# USB_UART_IMU.net
KiCad netlist of a schematic drawn in Altium Designer
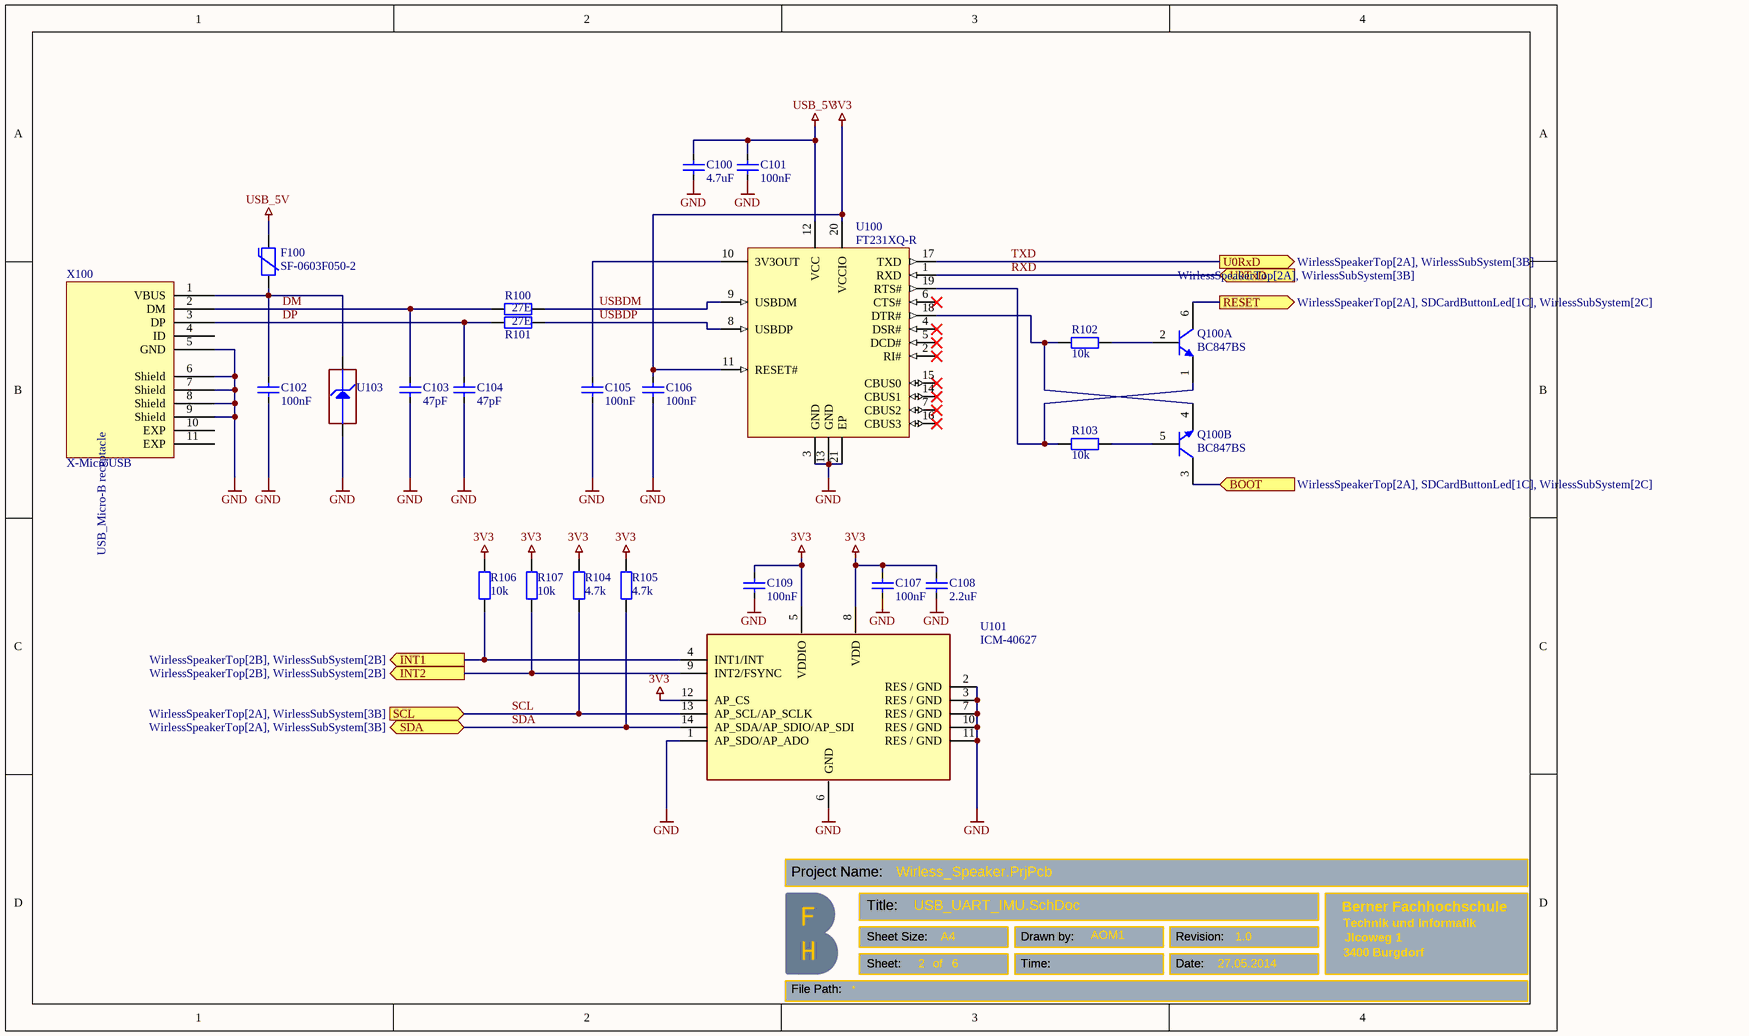
[diagram p0: USB_UART_IMU.SchDoc]

(export (version "E")
  (design (tool "Eeschema 10.0.6"))
  (components
    (comp (ref "C100")
      (value "4.7uF")
      (footprint "C-0603")
      (description "Multilayer Ceramic Capacitors MLCC")
      (fields (field (name "MANUFACTURER") "Murata Electronics") (field (name "MFR. PART NO.") "GRM18..."))
      (libsource (lib "WirelessAudioSpeaker") (part "C-SMD-0603"))
    )
    (comp (ref "C101")
      (value "100nF")
      (footprint "C-0603")
      (description "Multilayer Ceramic Capacitors MLCC")
      (fields (field (name "MANUFACTURER") "Murata Electronics") (field (name "MFR. PART NO.") "GRM18..."))
      (libsource (lib "WirelessAudioSpeaker") (part "C-SMD-0603"))
    )
    (comp (ref "C102")
      (value "100nF")
      (footprint "C-0603")
      (description "Multilayer Ceramic Capacitors MLCC")
      (fields (field (name "MANUFACTURER") "Murata Electronics") (field (name "MFR. PART NO.") "GRM18..."))
      (libsource (lib "WirelessAudioSpeaker") (part "C-SMD-0603"))
    )
    (comp (ref "C103")
      (value "47pF")
      (footprint "C-0603")
      (description "Multilayer Ceramic Capacitors MLCC")
      (fields (field (name "MANUFACTURER") "Murata Electronics") (field (name "MFR. PART NO.") "GRM18..."))
      (libsource (lib "WirelessAudioSpeaker") (part "C-SMD-0603"))
    )
    (comp (ref "C104")
      (value "47pF")
      (footprint "C-0603")
      (description "Multilayer Ceramic Capacitors MLCC")
      (fields (field (name "MANUFACTURER") "Murata Electronics") (field (name "MFR. PART NO.") "GRM18..."))
      (libsource (lib "WirelessAudioSpeaker") (part "C-SMD-0603"))
    )
    (comp (ref "C105")
      (value "100nF")
      (footprint "C-0603")
      (description "Multilayer Ceramic Capacitors MLCC")
      (fields (field (name "MANUFACTURER") "Murata Electronics") (field (name "MFR. PART NO.") "GRM18..."))
      (libsource (lib "WirelessAudioSpeaker") (part "C-SMD-0603"))
    )
    (comp (ref "C106")
      (value "100nF")
      (footprint "C-0603")
      (description "Multilayer Ceramic Capacitors MLCC")
      (fields (field (name "MANUFACTURER") "Murata Electronics") (field (name "MFR. PART NO.") "GRM18..."))
      (libsource (lib "WirelessAudioSpeaker") (part "C-SMD-0603"))
    )
    (comp (ref "C107")
      (value "100nF")
      (footprint "C-0603")
      (description "Multilayer Ceramic Capacitors MLCC")
      (fields (field (name "MANUFACTURER") "Murata Electronics") (field (name "MFR. PART NO.") "GRM18..."))
      (libsource (lib "WirelessAudioSpeaker") (part "C-SMD-0603"))
    )
    (comp (ref "C108")
      (value "2.2uF")
      (footprint "C-0603")
      (description "Multilayer Ceramic Capacitors MLCC")
      (fields (field (name "MANUFACTURER") "Murata Electronics") (field (name "MFR. PART NO.") "GRM18..."))
      (libsource (lib "WirelessAudioSpeaker") (part "C-SMD-0603"))
    )
    (comp (ref "C109")
      (value "100nF")
      (footprint "C-0603")
      (description "Multilayer Ceramic Capacitors MLCC")
      (fields (field (name "MANUFACTURER") "Murata Electronics") (field (name "MFR. PART NO.") "GRM18..."))
      (libsource (lib "WirelessAudioSpeaker") (part "C-SMD-0603"))
    )
    (comp (ref "F100")
      (value "SF-0603F050-2")
      (footprint "SMD-0603")
      (description "Surface Mount Fuses 0.5A Fast Acting")
      (fields (field (name "MANUFACTURER") "Bourns"))
      (libsource (lib "WirelessAudioSpeaker") (part "F-0603F050-2"))
    )
    (comp (ref "Q100")
      (value "BC847BS")
      (footprint "SOT-23-6")
      (description "Bipolares Transistor-Array, Universal, NPN, 45 V, 250 mW, 100 mA, 200 hFE, SC-88")
      (fields
        (field (name "MANUFACTURER") "Diodes Incorporated")
        (field (name "MFR. PART NO.") "BC847BS-7-F")
      )
      (libsource (lib "WirelessAudioSpeaker") (part "Q-BC847BS"))
    )
    (comp (ref "R100")
      (value "27E")
      (footprint "R-0603")
      (description "Thin Film Resistors - SMD  0.1W  1%")
      (fields (field (name "MFR. PART NO.") "MCU08050C*") (field (name "MANUFACTURER") "Vishay / Beyschlag"))
      (libsource (lib "WirelessAudioSpeaker") (part "R-SMD-0603"))
    )
    (comp (ref "R101")
      (value "27E")
      (footprint "R-0603")
      (description "Thin Film Resistors - SMD  0.1W  1%")
      (fields (field (name "MFR. PART NO.") "MCU08050C*") (field (name "MANUFACTURER") "Vishay / Beyschlag"))
      (libsource (lib "WirelessAudioSpeaker") (part "R-SMD-0603"))
    )
    (comp (ref "R102")
      (value "10k")
      (footprint "R-0603")
      (description "Thin Film Resistors - SMD  0.1W  1%")
      (fields (field (name "MFR. PART NO.") "MCU08050C*") (field (name "MANUFACTURER") "Vishay / Beyschlag"))
      (libsource (lib "WirelessAudioSpeaker") (part "R-SMD-0603"))
    )
    (comp (ref "R103")
      (value "10k")
      (footprint "R-0603")
      (description "Thin Film Resistors - SMD  0.1W  1%")
      (fields (field (name "MFR. PART NO.") "MCU08050C*") (field (name "MANUFACTURER") "Vishay / Beyschlag"))
      (libsource (lib "WirelessAudioSpeaker") (part "R-SMD-0603"))
    )
    (comp (ref "R104")
      (value "4.7k")
      (footprint "R-0603")
      (description "Thin Film Resistors - SMD  0.1W  1%")
      (fields (field (name "MFR. PART NO.") "MCU08050C*") (field (name "MANUFACTURER") "Vishay / Beyschlag"))
      (libsource (lib "") (part "R-SMD-0603_1"))
    )
    (comp (ref "R105")
      (value "4.7k")
      (footprint "R-0603")
      (description "Thin Film Resistors - SMD  0.1W  1%")
      (fields (field (name "MFR. PART NO.") "MCU08050C*") (field (name "MANUFACTURER") "Vishay / Beyschlag"))
      (libsource (lib "") (part "R-SMD-0603_1"))
    )
    (comp (ref "R106")
      (value "10k")
      (footprint "R-0603")
      (description "Thin Film Resistors - SMD  0.1W  1%")
      (fields (field (name "MFR. PART NO.") "MCU08050C*") (field (name "MANUFACTURER") "Vishay / Beyschlag"))
      (libsource (lib "") (part "R-SMD-0603_1"))
    )
    (comp (ref "R107")
      (value "10k")
      (footprint "R-0603")
      (description "Thin Film Resistors - SMD  0.1W  1%")
      (fields (field (name "MFR. PART NO.") "MCU08050C*") (field (name "MANUFACTURER") "Vishay / Beyschlag"))
      (libsource (lib "") (part "R-SMD-0603_1"))
    )
    (comp (ref "U100")
      (value "FT231XQ-R")
      (footprint "QFN-20-M")
      (description "USB Interface IC USB to Full Serial UART")
      (libsource (lib "WirelessAudioSpeaker") (part "U-FT231XQ-R"))
    )
    (comp (ref "U101")
      (value "ICM-40627")
      (footprint "LGA-14")
      (description "IMUs - Inertial Measurement Units Highly accurate MEMS based motion sensor")
      (fields (field (name "MANUFACTURER") "TDK InvenSense"))
      (libsource (lib "WirelessAudioSpeaker") (part "U-ICM-40627"))
    )
    (comp (ref "U103")
      (value "ESDA7P120-1U1M")
      (footprint "ESD_QFN1610_2N_1K_2A")
      (description "5V High power transient voltage suppressor")
      (fields (field (name "MANUFACTURER") "STMicroelectronics"))
      (libsource (lib "WirelessAudioSpeaker") (part "U-ESDA7P120-1U1M"))
    )
    (comp (ref "X100")
      (value "X-MicroUSB")
      (footprint "Micro-USB")
      (description "USB-Stecker MICRO USB B")
      (fields (field (name "MANUFACTURER") "Molex") (field (name "MFR. PART NO.") "105017-0001"))
      (libsource (lib "WirelessAudioSpeaker") (part "X-MicroUSB"))
    )
  )
  (nets
    (net (code "1") (name "/BOOT") (class "Default")
      (node (ref "Q100") (pin "3") (pinfunction "C2_3") (pintype "passive"))
    )
    (net (code "2") (name "/DM") (class "Default")
      (node (ref "C103") (pin "2") (pinfunction "2_2") (pintype "passive"))
      (node (ref "R100") (pin "1") (pinfunction "1_1") (pintype "passive"))
      (node (ref "X100") (pin "2") (pinfunction "DM_2") (pintype "passive"))
    )
    (net (code "3") (name "/DP") (class "Default")
      (node (ref "C104") (pin "2") (pinfunction "2_2") (pintype "passive"))
      (node (ref "R101") (pin "1") (pinfunction "1_1") (pintype "passive"))
      (node (ref "X100") (pin "3") (pinfunction "DP_3") (pintype "passive"))
    )
    (net (code "4") (name "/INT1") (class "Default")
      (node (ref "R106") (pin "1") (pinfunction "1_1") (pintype "passive"))
      (node (ref "U101") (pin "4") (pinfunction "INT1/INT_4") (pintype "passive"))
    )
    (net (code "5") (name "/INT2") (class "Default")
      (node (ref "R107") (pin "1") (pinfunction "1_1") (pintype "passive"))
      (node (ref "U101") (pin "9") (pinfunction "INT2/FSYNC_9") (pintype "passive"))
    )
    (net (code "6") (name "/RESET") (class "Default")
      (node (ref "Q100") (pin "6") (pinfunction "C1_6") (pintype "passive"))
    )
    (net (code "7") (name "/RXD") (class "Default")
      (node (ref "U100") (pin "1") (pinfunction "RXD_1") (pintype "input"))
    )
    (net (code "8") (name "/SCL") (class "Default")
      (node (ref "R104") (pin "1") (pinfunction "1_1") (pintype "passive"))
      (node (ref "U101") (pin "13") (pinfunction "AP_SCL/AP_SCLK_13") (pintype "passive"))
    )
    (net (code "9") (name "/SDA") (class "Default")
      (node (ref "R105") (pin "1") (pinfunction "1_1") (pintype "passive"))
      (node (ref "U101") (pin "14") (pinfunction "AP_SDA/AP_SDIO/AP_SDI_14") (pintype "passive"))
    )
    (net (code "10") (name "/TXD") (class "Default")
      (node (ref "U100") (pin "17") (pinfunction "TXD_17") (pintype "output"))
    )
    (net (code "11") (name "/USBDM") (class "Default")
      (node (ref "R100") (pin "2") (pinfunction "2_2") (pintype "passive"))
      (node (ref "U100") (pin "9") (pinfunction "USBDM_9") (pintype "input"))
    )
    (net (code "12") (name "/USBDP") (class "Default")
      (node (ref "R101") (pin "2") (pinfunction "2_2") (pintype "passive"))
      (node (ref "U100") (pin "8") (pinfunction "USBDP_8") (pintype "input"))
    )
    (net (code "13") (name "3V3") (class "Default")
      (node (ref "C106") (pin "2") (pinfunction "2_2") (pintype "passive"))
      (node (ref "C107") (pin "2") (pinfunction "2_2") (pintype "passive"))
      (node (ref "C108") (pin "2") (pinfunction "2_2") (pintype "passive"))
      (node (ref "C109") (pin "2") (pinfunction "2_2") (pintype "passive"))
      (node (ref "R104") (pin "2") (pinfunction "2_2") (pintype "passive"))
      (node (ref "R105") (pin "2") (pinfunction "2_2") (pintype "passive"))
      (node (ref "R106") (pin "2") (pinfunction "2_2") (pintype "passive"))
      (node (ref "R107") (pin "2") (pinfunction "2_2") (pintype "passive"))
      (node (ref "U100") (pin "11") (pinfunction "RESET#_11") (pintype "input"))
      (node (ref "U100") (pin "20") (pinfunction "VCCIO_20") (pintype "power_in"))
      (node (ref "U101") (pin "12") (pinfunction "AP_CS_12") (pintype "passive"))
      (node (ref "U101") (pin "5") (pinfunction "VDDIO_5") (pintype "passive"))
      (node (ref "U101") (pin "8") (pinfunction "VDD_8") (pintype "passive"))
    )
    (net (code "14") (name "GND") (class "Default")
      (node (ref "C100") (pin "1") (pinfunction "1_1") (pintype "passive"))
      (node (ref "C101") (pin "1") (pinfunction "1_1") (pintype "passive"))
      (node (ref "C102") (pin "1") (pinfunction "1_1") (pintype "passive"))
      (node (ref "C103") (pin "1") (pinfunction "1_1") (pintype "passive"))
      (node (ref "C104") (pin "1") (pinfunction "1_1") (pintype "passive"))
      (node (ref "C105") (pin "1") (pinfunction "1_1") (pintype "passive"))
      (node (ref "C106") (pin "1") (pinfunction "1_1") (pintype "passive"))
      (node (ref "C107") (pin "1") (pinfunction "1_1") (pintype "passive"))
      (node (ref "C108") (pin "1") (pinfunction "1_1") (pintype "passive"))
      (node (ref "C109") (pin "1") (pinfunction "1_1") (pintype "passive"))
      (node (ref "U100") (pin "13") (pinfunction "GND_13") (pintype "power_in"))
      (node (ref "U100") (pin "21") (pinfunction "EP_21") (pintype "power_in"))
      (node (ref "U100") (pin "3") (pinfunction "GND_3") (pintype "power_in"))
      (node (ref "U101") (pin "1") (pinfunction "AP_SDO/AP_ADO_1") (pintype "passive"))
      (node (ref "U101") (pin "10") (pinfunction "RES_/_GND_10") (pintype "passive"))
      (node (ref "U101") (pin "11") (pinfunction "RES_/_GND_11") (pintype "passive"))
      (node (ref "U101") (pin "2") (pinfunction "RES_/_GND_2") (pintype "passive"))
      (node (ref "U101") (pin "3") (pinfunction "RES_/_GND_3") (pintype "passive"))
      (node (ref "U101") (pin "6") (pinfunction "GND_6") (pintype "passive"))
      (node (ref "U101") (pin "7") (pinfunction "RES_/_GND_7") (pintype "passive"))
      (node (ref "U103") (pin "2") (pinfunction "GND_2") (pintype "passive"))
      (node (ref "X100") (pin "5") (pinfunction "GND_5") (pintype "passive"))
      (node (ref "X100") (pin "6") (pinfunction "Shield_6") (pintype "passive"))
      (node (ref "X100") (pin "7") (pinfunction "Shield_7") (pintype "passive"))
      (node (ref "X100") (pin "8") (pinfunction "Shield_8") (pintype "passive"))
      (node (ref "X100") (pin "9") (pinfunction "Shield_9") (pintype "passive"))
    )
    (net (code "15") (name "Net-(Q100A-B1)") (class "Default")
      (node (ref "Q100") (pin "2") (pinfunction "B1_2") (pintype "passive"))
      (node (ref "R102") (pin "2") (pinfunction "2_2") (pintype "passive"))
    )
    (net (code "16") (name "Net-(Q100A-E1)") (class "Default")
      (node (ref "Q100") (pin "1") (pinfunction "E1_1") (pintype "passive"))
      (node (ref "R103") (pin "1") (pinfunction "1_1") (pintype "passive"))
      (node (ref "U100") (pin "19") (pinfunction "RTS#_19") (pintype "output"))
    )
    (net (code "17") (name "Net-(Q100B-B2)") (class "Default")
      (node (ref "Q100") (pin "5") (pinfunction "B2_5") (pintype "passive"))
      (node (ref "R103") (pin "2") (pinfunction "2_2") (pintype "passive"))
    )
    (net (code "18") (name "Net-(Q100B-E2)") (class "Default")
      (node (ref "Q100") (pin "4") (pinfunction "E2_4") (pintype "passive"))
      (node (ref "R102") (pin "1") (pinfunction "1_1") (pintype "passive"))
      (node (ref "U100") (pin "18") (pinfunction "DTR#_18") (pintype "output"))
    )
    (net (code "19") (name "Net-(U100-3V3OUT)") (class "Default")
      (node (ref "C105") (pin "2") (pinfunction "2_2") (pintype "passive"))
      (node (ref "U100") (pin "10") (pinfunction "3V3OUT_10") (pintype "power_in"))
    )
    (net (code "20") (name "Net-(U103-IO1)") (class "Default")
      (node (ref "C102") (pin "2") (pinfunction "2_2") (pintype "passive"))
      (node (ref "F100") (pin "1") (pinfunction "1_1") (pintype "passive"))
      (node (ref "U103") (pin "1") (pinfunction "IO1_1") (pintype "passive"))
      (node (ref "X100") (pin "1") (pinfunction "VBUS_1") (pintype "passive"))
    )
    (net (code "21") (name "USB_5V") (class "Default")
      (node (ref "C100") (pin "2") (pinfunction "2_2") (pintype "passive"))
      (node (ref "C101") (pin "2") (pinfunction "2_2") (pintype "passive"))
      (node (ref "F100") (pin "2") (pinfunction "2_2") (pintype "passive"))
      (node (ref "U100") (pin "12") (pinfunction "VCC_12") (pintype "power_in"))
    )
    (net (code "22") (name "unconnected-(U100-CBUS0-Pad15)") (class "Default")
      (node (ref "U100") (pin "15") (pinfunction "CBUS0_15") (pintype "bidirectional+no_connect"))
    )
    (net (code "23") (name "unconnected-(U100-CBUS1-Pad14)") (class "Default")
      (node (ref "U100") (pin "14") (pinfunction "CBUS1_14") (pintype "bidirectional+no_connect"))
    )
    (net (code "24") (name "unconnected-(U100-CBUS2-Pad7)") (class "Default")
      (node (ref "U100") (pin "7") (pinfunction "CBUS2_7") (pintype "bidirectional+no_connect"))
    )
    (net (code "25") (name "unconnected-(U100-CBUS3-Pad16)") (class "Default")
      (node (ref "U100") (pin "16") (pinfunction "CBUS3_16") (pintype "bidirectional+no_connect"))
    )
    (net (code "26") (name "unconnected-(U100-CTS#-Pad6)") (class "Default")
      (node (ref "U100") (pin "6") (pinfunction "CTS#_6") (pintype "input+no_connect"))
    )
    (net (code "27") (name "unconnected-(U100-DCD#-Pad5)") (class "Default")
      (node (ref "U100") (pin "5") (pinfunction "DCD#_5") (pintype "input+no_connect"))
    )
    (net (code "28") (name "unconnected-(U100-DSR#-Pad4)") (class "Default")
      (node (ref "U100") (pin "4") (pinfunction "DSR#_4") (pintype "input+no_connect"))
    )
    (net (code "29") (name "unconnected-(U100-RI#-Pad2)") (class "Default")
      (node (ref "U100") (pin "2") (pinfunction "RI#_2") (pintype "input+no_connect"))
    )
    (net (code "30") (name "unconnected-(X100-EXP-Pad10)") (class "Default")
      (node (ref "X100") (pin "10") (pinfunction "EXP_10") (pintype "passive"))
    )
    (net (code "31") (name "unconnected-(X100-EXP-Pad11)") (class "Default")
      (node (ref "X100") (pin "11") (pinfunction "EXP_11") (pintype "passive"))
    )
    (net (code "32") (name "unconnected-(X100-ID-Pad4)") (class "Default")
      (node (ref "X100") (pin "4") (pinfunction "ID_4") (pintype "passive"))
    )
  )
)
